# penvmon.net
KiCad netlist of a schematic drawn in EAGLE
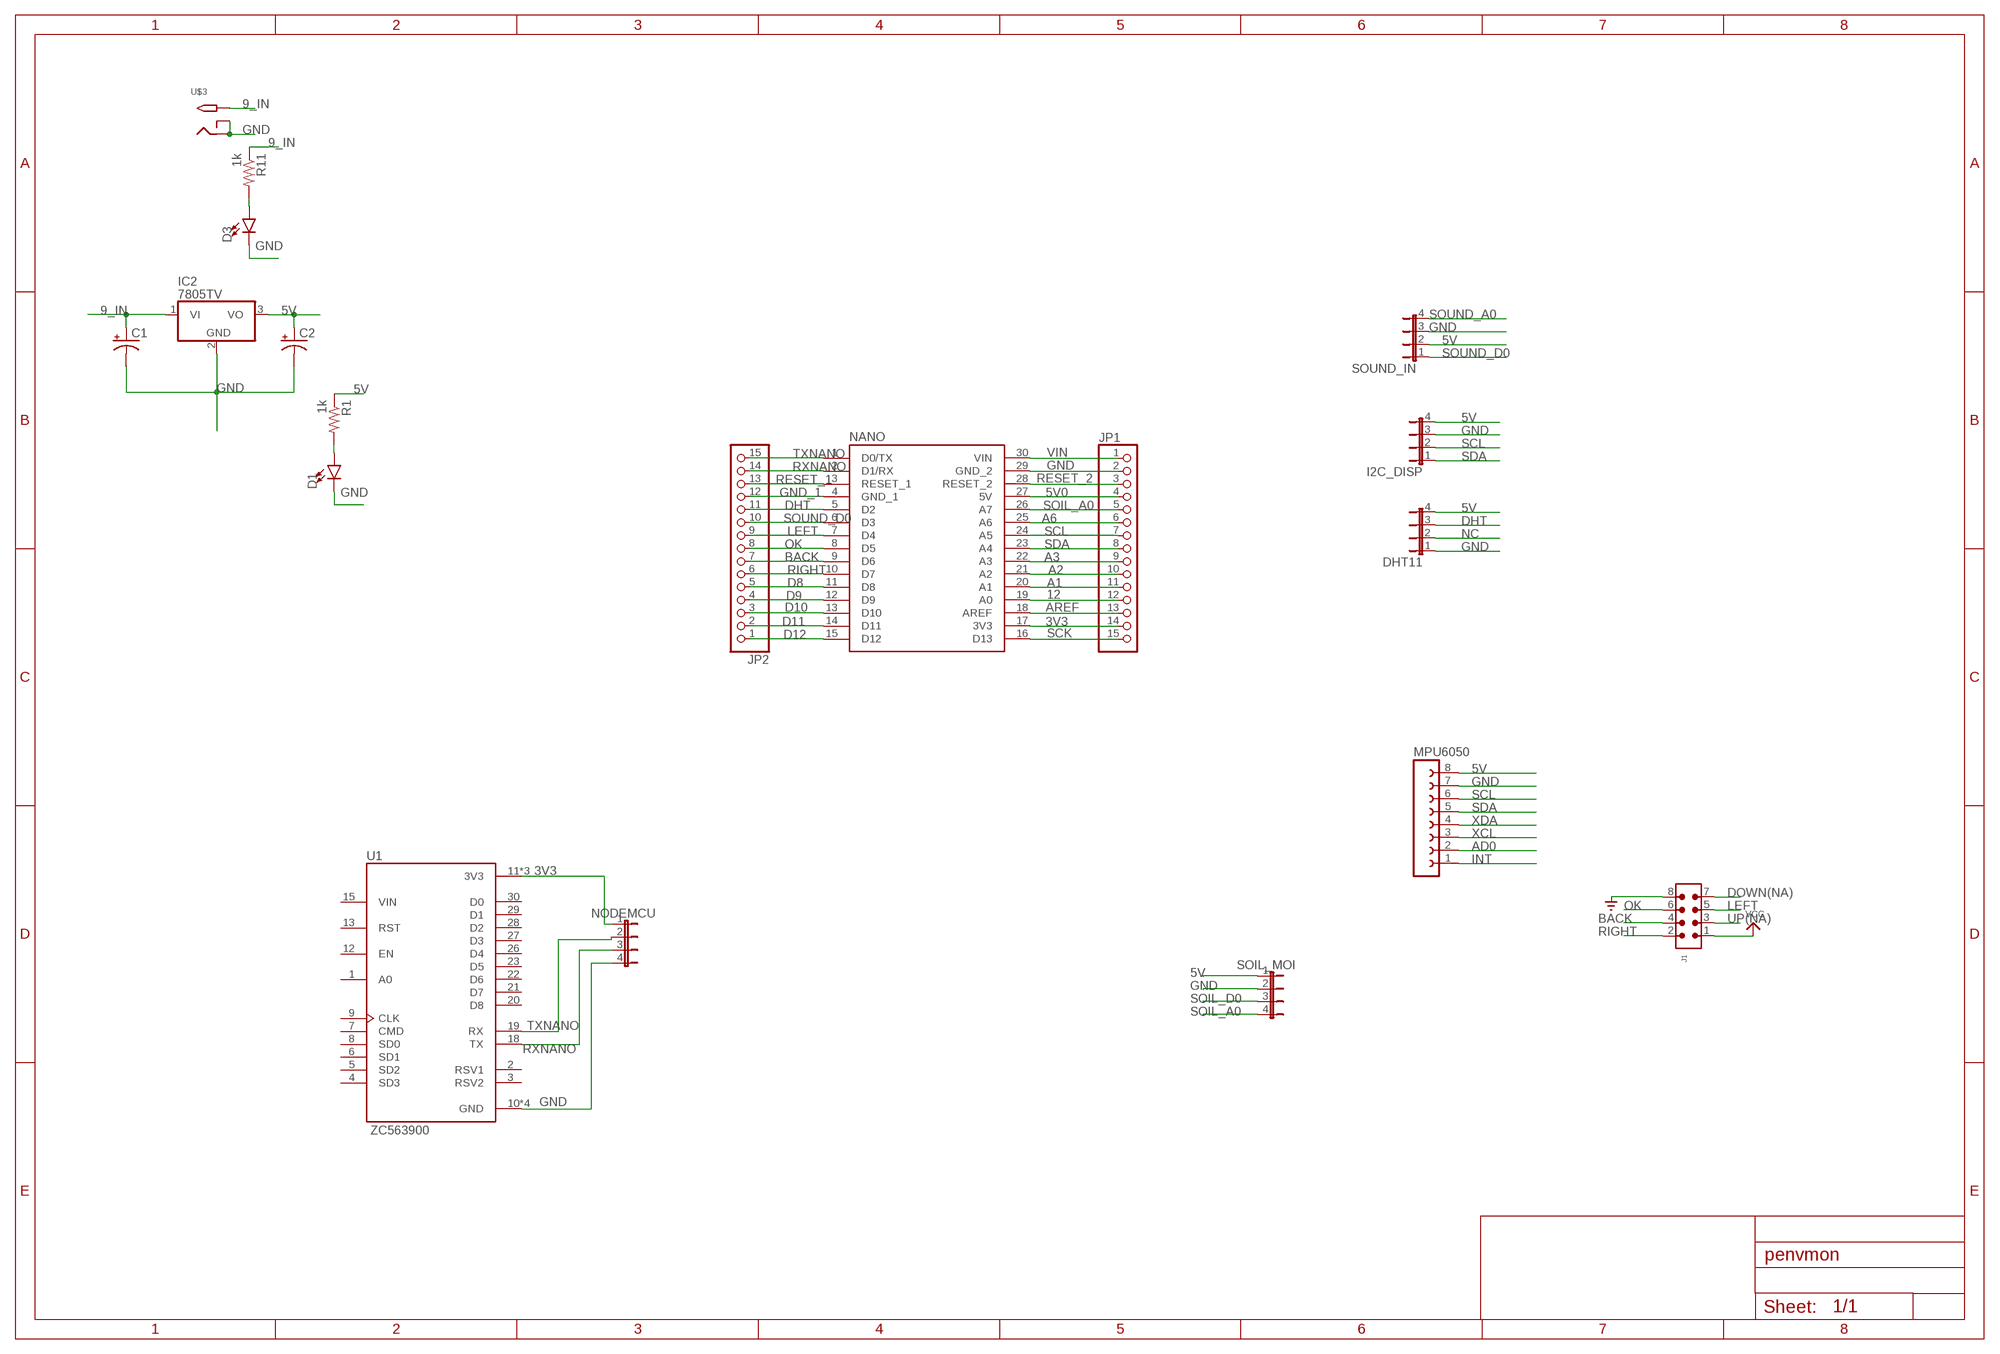
[diagram p0: schematic, sheet 1]

(export (version "E")
  (design (tool "Eeschema 10.0.6"))
  (components
    (comp (ref "C1")
      (value "CPOL-USE3.5-8")
      (footprint "eagle-import:E3,5-8")
      (libsource (lib "eagle-import") (part "CPOL-USE3.5-8"))
    )
    (comp (ref "C2")
      (value "CPOL-USE3.5-8")
      (footprint "eagle-import:E3,5-8")
      (libsource (lib "eagle-import") (part "CPOL-USE3.5-8"))
    )
    (comp (ref "D1")
      (value "LED3MM")
      (footprint "eagle-import:LED_3MM")
      (libsource (lib "eagle-import") (part "LED3MM"))
    )
    (comp (ref "D3")
      (value "LED3MM")
      (footprint "eagle-import:LED_3MM")
      (libsource (lib "eagle-import") (part "LED3MM"))
    )
    (comp (ref "DHT11")
      (value "JP4E")
      (footprint "eagle-import:JP4")
      (libsource (lib "eagle-import") (part "JP4E"))
    )
    (comp (ref "I2C_DISP")
      (value "JP4E")
      (footprint "eagle-import:JP4")
      (libsource (lib "eagle-import") (part "JP4E"))
    )
    (comp (ref "IC2")
      (value "7805TV")
      (footprint "eagle-import:TO220V")
      (libsource (lib "eagle-import") (part "78TV05"))
    )
    (comp (ref "J1")
      (value "6120XX21621_61200821621")
      (footprint "eagle-import:61200821621")
      (libsource (lib "eagle-import") (part "6120XX21621_61200821621"))
    )
    (comp (ref "JP1")
      (value "PINHD-1X15")
      (footprint "eagle-import:1X15")
      (libsource (lib "eagle-import") (part "PINHD-1X15"))
    )
    (comp (ref "JP2")
      (value "PINHD-1X15")
      (footprint "eagle-import:1X15")
      (libsource (lib "eagle-import") (part "PINHD-1X15"))
    )
    (comp (ref "MPU6050")
      (value "FE08-1")
      (footprint "eagle-import:FE08")
      (libsource (lib "eagle-import") (part "FE08-1"))
    )
    (comp (ref "NANO")
      (value "A000005")
      (footprint "eagle-import:MODULE_A000005")
      (fields (field (name "MF") "Arduino"))
      (libsource (lib "eagle-import") (part "A000005"))
    )
    (comp (ref "NODEMCU")
      (value "JP4E")
      (footprint "eagle-import:JP4")
      (libsource (lib "eagle-import") (part "JP4E"))
    )
    (comp (ref "R1")
      (value "1k")
      (footprint "eagle-import:M0805")
      (libsource (lib "eagle-import") (part "R-US_M0805"))
    )
    (comp (ref "R11")
      (value "1k")
      (footprint "eagle-import:M0805")
      (libsource (lib "eagle-import") (part "R-US_M0805"))
    )
    (comp (ref "SOIL_MOI")
      (value "JP4E")
      (footprint "eagle-import:JP4")
      (libsource (lib "eagle-import") (part "JP4E"))
    )
    (comp (ref "SOUND_IN")
      (value "JP4E")
      (footprint "eagle-import:JP4")
      (libsource (lib "eagle-import") (part "JP4E"))
    )
    (comp (ref "U$3")
      (value "2.1MMJACKTHM")
      (footprint "eagle-import:PJ-102A")
      (libsource (lib "eagle-import") (part "2.1MMJACKTHM"))
    )
    (comp (ref "U1")
      (value "ZC563900")
      (footprint "eagle-import:MODULE_ZC563900")
      (fields (field (name "MF") "YKS"))
      (libsource (lib "eagle-import") (part "ZC563900"))
    )
  )
  (nets
    (net (code "1") (name "/3V3") (class "Default")
      (node (ref "JP1") (pin "14") (pinfunction "14_14") (pintype "passive"))
      (node (ref "NANO") (pin "17") (pinfunction "3V3_17") (pintype "power_in"))
      (node (ref "NODEMCU") (pin "1") (pinfunction "1_1") (pintype "passive"))
      (node (ref "U1") (pin "11") (pinfunction "3V3_11") (pintype "power_in"))
      (node (ref "U1") (pin "16") (pinfunction "3V3_16") (pintype "power_in"))
      (node (ref "U1") (pin "25") (pinfunction "3V3_25") (pintype "power_in"))
    )
    (net (code "2") (name "/5V") (class "Default")
      (node (ref "C2") (pin "+") (pinfunction "+_+") (pintype "passive"))
      (node (ref "DHT11") (pin "4") (pinfunction "4_4") (pintype "passive"))
      (node (ref "I2C_DISP") (pin "4") (pinfunction "4_4") (pintype "passive"))
      (node (ref "IC2") (pin "3") (pinfunction "VO_3") (pintype "passive"))
      (node (ref "MPU6050") (pin "8") (pinfunction "8_8") (pintype "passive"))
      (node (ref "R1") (pin "1") (pinfunction "1_1") (pintype "passive"))
      (node (ref "SOIL_MOI") (pin "1") (pinfunction "1_1") (pintype "passive"))
      (node (ref "SOUND_IN") (pin "2") (pinfunction "2_2") (pintype "passive"))
    )
    (net (code "3") (name "/5V0") (class "Default")
      (node (ref "JP1") (pin "4") (pinfunction "4_4") (pintype "passive"))
      (node (ref "NANO") (pin "27") (pinfunction "5V_27") (pintype "power_in"))
    )
    (net (code "4") (name "/9_IN") (class "Default")
      (node (ref "C1") (pin "+") (pinfunction "+_+") (pintype "passive"))
      (node (ref "IC2") (pin "1") (pinfunction "VI_1") (pintype "input"))
      (node (ref "R11") (pin "1") (pinfunction "1_1") (pintype "passive"))
      (node (ref "U$3") (pin "TIP") (pinfunction "TIP_TIP") (pintype "bidirectional"))
    )
    (net (code "5") (name "/12") (class "Default")
      (node (ref "JP1") (pin "12") (pinfunction "12_12") (pintype "passive"))
      (node (ref "NANO") (pin "19") (pinfunction "A0_19") (pintype "input"))
    )
    (net (code "6") (name "/A1") (class "Default")
      (node (ref "JP1") (pin "11") (pinfunction "11_11") (pintype "passive"))
      (node (ref "NANO") (pin "20") (pinfunction "A1_20") (pintype "input"))
    )
    (net (code "7") (name "/A2") (class "Default")
      (node (ref "JP1") (pin "10") (pinfunction "10_10") (pintype "passive"))
      (node (ref "NANO") (pin "21") (pinfunction "A2_21") (pintype "input"))
    )
    (net (code "8") (name "/A3") (class "Default")
      (node (ref "JP1") (pin "9") (pinfunction "9_9") (pintype "passive"))
      (node (ref "NANO") (pin "22") (pinfunction "A3_22") (pintype "input"))
    )
    (net (code "9") (name "/A6") (class "Default")
      (node (ref "JP1") (pin "6") (pinfunction "6_6") (pintype "passive"))
      (node (ref "NANO") (pin "25") (pinfunction "A6_25") (pintype "input"))
    )
    (net (code "10") (name "/AD0") (class "Default")
      (node (ref "MPU6050") (pin "2") (pinfunction "2_2") (pintype "passive"))
    )
    (net (code "11") (name "/AREF") (class "Default")
      (node (ref "JP1") (pin "13") (pinfunction "13_13") (pintype "passive"))
      (node (ref "NANO") (pin "18") (pinfunction "AREF_18") (pintype "input"))
    )
    (net (code "12") (name "/BACK") (class "Default")
      (node (ref "J1") (pin "4") (pinfunction "4_4") (pintype "passive"))
      (node (ref "JP2") (pin "7") (pinfunction "7_7") (pintype "passive"))
      (node (ref "NANO") (pin "9") (pinfunction "D6_9") (pintype "bidirectional"))
    )
    (net (code "13") (name "/D8") (class "Default")
      (node (ref "JP2") (pin "5") (pinfunction "5_5") (pintype "passive"))
      (node (ref "NANO") (pin "11") (pinfunction "D8_11") (pintype "bidirectional"))
    )
    (net (code "14") (name "/D9") (class "Default")
      (node (ref "JP2") (pin "4") (pinfunction "4_4") (pintype "passive"))
      (node (ref "NANO") (pin "12") (pinfunction "D9_12") (pintype "bidirectional"))
    )
    (net (code "15") (name "/D10") (class "Default")
      (node (ref "JP2") (pin "3") (pinfunction "3_3") (pintype "passive"))
      (node (ref "NANO") (pin "13") (pinfunction "D10_13") (pintype "bidirectional"))
    )
    (net (code "16") (name "/D11") (class "Default")
      (node (ref "JP2") (pin "2") (pinfunction "2_2") (pintype "passive"))
      (node (ref "NANO") (pin "14") (pinfunction "D11_14") (pintype "bidirectional"))
    )
    (net (code "17") (name "/D12") (class "Default")
      (node (ref "JP2") (pin "1") (pinfunction "1_1") (pintype "passive"))
      (node (ref "NANO") (pin "15") (pinfunction "D12_15") (pintype "bidirectional"))
    )
    (net (code "18") (name "/DHT") (class "Default")
      (node (ref "DHT11") (pin "3") (pinfunction "3_3") (pintype "passive"))
      (node (ref "JP2") (pin "11") (pinfunction "11_11") (pintype "passive"))
      (node (ref "NANO") (pin "5") (pinfunction "D2_5") (pintype "bidirectional"))
    )
    (net (code "19") (name "/DOWN(NA)") (class "Default")
      (node (ref "J1") (pin "7") (pinfunction "7_7") (pintype "passive"))
    )
    (net (code "20") (name "/GND_1") (class "Default")
      (node (ref "JP2") (pin "12") (pinfunction "12_12") (pintype "passive"))
      (node (ref "NANO") (pin "4") (pinfunction "GND_1_4") (pintype "power_in"))
    )
    (net (code "21") (name "/INT") (class "Default")
      (node (ref "MPU6050") (pin "1") (pinfunction "1_1") (pintype "passive"))
    )
    (net (code "22") (name "/LEFT") (class "Default")
      (node (ref "J1") (pin "5") (pinfunction "5_5") (pintype "passive"))
      (node (ref "JP2") (pin "9") (pinfunction "9_9") (pintype "passive"))
      (node (ref "NANO") (pin "7") (pinfunction "D4_7") (pintype "bidirectional"))
    )
    (net (code "23") (name "/NC") (class "Default")
      (node (ref "DHT11") (pin "2") (pinfunction "2_2") (pintype "passive"))
    )
    (net (code "24") (name "/OK") (class "Default")
      (node (ref "J1") (pin "6") (pinfunction "6_6") (pintype "passive"))
      (node (ref "JP2") (pin "8") (pinfunction "8_8") (pintype "passive"))
      (node (ref "NANO") (pin "8") (pinfunction "D5_8") (pintype "bidirectional"))
    )
    (net (code "25") (name "/RESET_1") (class "Default")
      (node (ref "JP2") (pin "13") (pinfunction "13_13") (pintype "passive"))
      (node (ref "NANO") (pin "3") (pinfunction "RESET_1_3") (pintype "input"))
    )
    (net (code "26") (name "/RESET_2") (class "Default")
      (node (ref "JP1") (pin "3") (pinfunction "3_3") (pintype "passive"))
      (node (ref "NANO") (pin "28") (pinfunction "RESET_2_28") (pintype "input"))
    )
    (net (code "27") (name "/RIGHT") (class "Default")
      (node (ref "J1") (pin "2") (pinfunction "2_2") (pintype "passive"))
      (node (ref "JP2") (pin "6") (pinfunction "6_6") (pintype "passive"))
      (node (ref "NANO") (pin "10") (pinfunction "D7_10") (pintype "bidirectional"))
    )
    (net (code "28") (name "/RXNANO") (class "Default")
      (node (ref "JP2") (pin "14") (pinfunction "14_14") (pintype "passive"))
      (node (ref "NANO") (pin "2") (pinfunction "D1/RX_2") (pintype "bidirectional"))
      (node (ref "NODEMCU") (pin "3") (pinfunction "3_3") (pintype "passive"))
      (node (ref "U1") (pin "18") (pinfunction "TX_18") (pintype "bidirectional"))
    )
    (net (code "29") (name "/SCK") (class "Default")
      (node (ref "JP1") (pin "15") (pinfunction "15_15") (pintype "passive"))
      (node (ref "NANO") (pin "16") (pinfunction "D13_16") (pintype "bidirectional"))
    )
    (net (code "30") (name "/SCL") (class "Default")
      (node (ref "I2C_DISP") (pin "2") (pinfunction "2_2") (pintype "passive"))
      (node (ref "JP1") (pin "7") (pinfunction "7_7") (pintype "passive"))
      (node (ref "MPU6050") (pin "6") (pinfunction "6_6") (pintype "passive"))
      (node (ref "NANO") (pin "24") (pinfunction "A5_24") (pintype "input"))
    )
    (net (code "31") (name "/SDA") (class "Default")
      (node (ref "I2C_DISP") (pin "1") (pinfunction "1_1") (pintype "passive"))
      (node (ref "JP1") (pin "8") (pinfunction "8_8") (pintype "passive"))
      (node (ref "MPU6050") (pin "5") (pinfunction "5_5") (pintype "passive"))
      (node (ref "NANO") (pin "23") (pinfunction "A4_23") (pintype "input"))
    )
    (net (code "32") (name "/SOIL_A0") (class "Default")
      (node (ref "JP1") (pin "5") (pinfunction "5_5") (pintype "passive"))
      (node (ref "NANO") (pin "26") (pinfunction "A7_26") (pintype "input"))
      (node (ref "SOIL_MOI") (pin "4") (pinfunction "4_4") (pintype "passive"))
    )
    (net (code "33") (name "/SOIL_D0") (class "Default")
      (node (ref "SOIL_MOI") (pin "3") (pinfunction "3_3") (pintype "passive"))
    )
    (net (code "34") (name "/SOUND_A0") (class "Default")
      (node (ref "SOUND_IN") (pin "4") (pinfunction "4_4") (pintype "passive"))
    )
    (net (code "35") (name "/SOUND_D0") (class "Default")
      (node (ref "JP2") (pin "10") (pinfunction "10_10") (pintype "passive"))
      (node (ref "NANO") (pin "6") (pinfunction "D3_6") (pintype "bidirectional"))
      (node (ref "SOUND_IN") (pin "1") (pinfunction "1_1") (pintype "passive"))
    )
    (net (code "36") (name "/TXNANO") (class "Default")
      (node (ref "JP2") (pin "15") (pinfunction "15_15") (pintype "passive"))
      (node (ref "NANO") (pin "1") (pinfunction "D0/TX_1") (pintype "bidirectional"))
      (node (ref "NODEMCU") (pin "2") (pinfunction "2_2") (pintype "passive"))
      (node (ref "U1") (pin "19") (pinfunction "RX_19") (pintype "bidirectional"))
    )
    (net (code "37") (name "/UP(NA)") (class "Default")
      (node (ref "J1") (pin "3") (pinfunction "3_3") (pintype "passive"))
    )
    (net (code "38") (name "/VIN") (class "Default")
      (node (ref "JP1") (pin "1") (pinfunction "1_1") (pintype "passive"))
      (node (ref "NANO") (pin "30") (pinfunction "VIN_30") (pintype "power_in"))
    )
    (net (code "39") (name "/XCL") (class "Default")
      (node (ref "MPU6050") (pin "3") (pinfunction "3_3") (pintype "passive"))
    )
    (net (code "40") (name "/XDA") (class "Default")
      (node (ref "MPU6050") (pin "4") (pinfunction "4_4") (pintype "passive"))
    )
    (net (code "41") (name "Net-(D1-PadA)") (class "Default")
      (node (ref "D1") (pin "A") (pinfunction "A_A") (pintype "passive"))
      (node (ref "R1") (pin "2") (pinfunction "2_2") (pintype "passive"))
    )
    (net (code "42") (name "Net-(D3-PadA)") (class "Default")
      (node (ref "D3") (pin "A") (pinfunction "A_A") (pintype "passive"))
      (node (ref "R11") (pin "2") (pinfunction "2_2") (pintype "passive"))
    )
    (net (code "43") (name "SUPPLY0_GND_") (class "Default")
      (node (ref "C1") (pin "-") (pinfunction "-_-") (pintype "passive"))
      (node (ref "C2") (pin "-") (pinfunction "-_-") (pintype "passive"))
      (node (ref "D1") (pin "K") (pinfunction "C_K") (pintype "passive"))
      (node (ref "D3") (pin "K") (pinfunction "C_K") (pintype "passive"))
      (node (ref "DHT11") (pin "1") (pinfunction "1_1") (pintype "passive"))
      (node (ref "I2C_DISP") (pin "3") (pinfunction "3_3") (pintype "passive"))
      (node (ref "IC2") (pin "2") (pinfunction "GND_2") (pintype "passive"))
      (node (ref "J1") (pin "8") (pinfunction "8_8") (pintype "passive"))
      (node (ref "JP1") (pin "2") (pinfunction "2_2") (pintype "passive"))
      (node (ref "MPU6050") (pin "7") (pinfunction "7_7") (pintype "passive"))
      (node (ref "NANO") (pin "29") (pinfunction "GND_2_29") (pintype "power_in"))
      (node (ref "NODEMCU") (pin "4") (pinfunction "4_4") (pintype "passive"))
      (node (ref "SOIL_MOI") (pin "2") (pinfunction "2_2") (pintype "passive"))
      (node (ref "SOUND_IN") (pin "3") (pinfunction "3_3") (pintype "passive"))
      (node (ref "U$3") (pin "RING") (pinfunction "RING_RING") (pintype "bidirectional"))
      (node (ref "U$3") (pin "RING_SW") (pinfunction "RING_SW_RING_SW") (pintype "bidirectional"))
      (node (ref "U1") (pin "10") (pinfunction "GND_10") (pintype "power_in"))
      (node (ref "U1") (pin "14") (pinfunction "GND_14") (pintype "power_in"))
      (node (ref "U1") (pin "17") (pinfunction "GND_17") (pintype "power_in"))
      (node (ref "U1") (pin "24") (pinfunction "GND_24") (pintype "power_in"))
    )
    (net (code "44") (name "VCC") (class "Default")
      (node (ref "J1") (pin "1") (pinfunction "1_1") (pintype "passive"))
    )
    (net (code "45") (name "unconnected-(U1-A0-Pad1)") (class "Default")
      (node (ref "U1") (pin "1") (pinfunction "A0_1") (pintype "input"))
    )
    (net (code "46") (name "unconnected-(U1-CLK-Pad9)") (class "Default")
      (node (ref "U1") (pin "9") (pinfunction "CLK_9") (pintype "input"))
    )
    (net (code "47") (name "unconnected-(U1-CMD-Pad7)") (class "Default")
      (node (ref "U1") (pin "7") (pinfunction "CMD_7") (pintype "input"))
    )
    (net (code "48") (name "unconnected-(U1-D0-Pad30)") (class "Default")
      (node (ref "U1") (pin "30") (pinfunction "D0_30") (pintype "bidirectional"))
    )
    (net (code "49") (name "unconnected-(U1-D1-Pad29)") (class "Default")
      (node (ref "U1") (pin "29") (pinfunction "D1_29") (pintype "bidirectional"))
    )
    (net (code "50") (name "unconnected-(U1-D2-Pad28)") (class "Default")
      (node (ref "U1") (pin "28") (pinfunction "D2_28") (pintype "bidirectional"))
    )
    (net (code "51") (name "unconnected-(U1-D3-Pad27)") (class "Default")
      (node (ref "U1") (pin "27") (pinfunction "D3_27") (pintype "bidirectional"))
    )
    (net (code "52") (name "unconnected-(U1-D4-Pad26)") (class "Default")
      (node (ref "U1") (pin "26") (pinfunction "D4_26") (pintype "bidirectional"))
    )
    (net (code "53") (name "unconnected-(U1-D5-Pad23)") (class "Default")
      (node (ref "U1") (pin "23") (pinfunction "D5_23") (pintype "bidirectional"))
    )
    (net (code "54") (name "unconnected-(U1-D6-Pad22)") (class "Default")
      (node (ref "U1") (pin "22") (pinfunction "D6_22") (pintype "bidirectional"))
    )
    (net (code "55") (name "unconnected-(U1-D7-Pad21)") (class "Default")
      (node (ref "U1") (pin "21") (pinfunction "D7_21") (pintype "bidirectional"))
    )
    (net (code "56") (name "unconnected-(U1-D8-Pad20)") (class "Default")
      (node (ref "U1") (pin "20") (pinfunction "D8_20") (pintype "bidirectional"))
    )
    (net (code "57") (name "unconnected-(U1-EN-Pad12)") (class "Default")
      (node (ref "U1") (pin "12") (pinfunction "EN_12") (pintype "input"))
    )
    (net (code "58") (name "unconnected-(U1-RST-Pad13)") (class "Default")
      (node (ref "U1") (pin "13") (pinfunction "RST_13") (pintype "input"))
    )
    (net (code "59") (name "unconnected-(U1-RSV1-Pad2)") (class "Default")
      (node (ref "U1") (pin "2") (pinfunction "RSV1_2") (pintype "passive"))
    )
    (net (code "60") (name "unconnected-(U1-RSV2-Pad3)") (class "Default")
      (node (ref "U1") (pin "3") (pinfunction "RSV2_3") (pintype "passive"))
    )
    (net (code "61") (name "unconnected-(U1-SD0-Pad8)") (class "Default")
      (node (ref "U1") (pin "8") (pinfunction "SD0_8") (pintype "bidirectional"))
    )
    (net (code "62") (name "unconnected-(U1-SD1-Pad6)") (class "Default")
      (node (ref "U1") (pin "6") (pinfunction "SD1_6") (pintype "bidirectional"))
    )
    (net (code "63") (name "unconnected-(U1-SD2-Pad5)") (class "Default")
      (node (ref "U1") (pin "5") (pinfunction "SD2_5") (pintype "bidirectional"))
    )
    (net (code "64") (name "unconnected-(U1-SD3-Pad4)") (class "Default")
      (node (ref "U1") (pin "4") (pinfunction "SD3_4") (pintype "bidirectional"))
    )
    (net (code "65") (name "unconnected-(U1-VIN-Pad15)") (class "Default")
      (node (ref "U1") (pin "15") (pinfunction "VIN_15") (pintype "input"))
    )
  )
)
